# Transmissor_Ignitor.net
KiCad netlist of a schematic drawn in Altium Designer
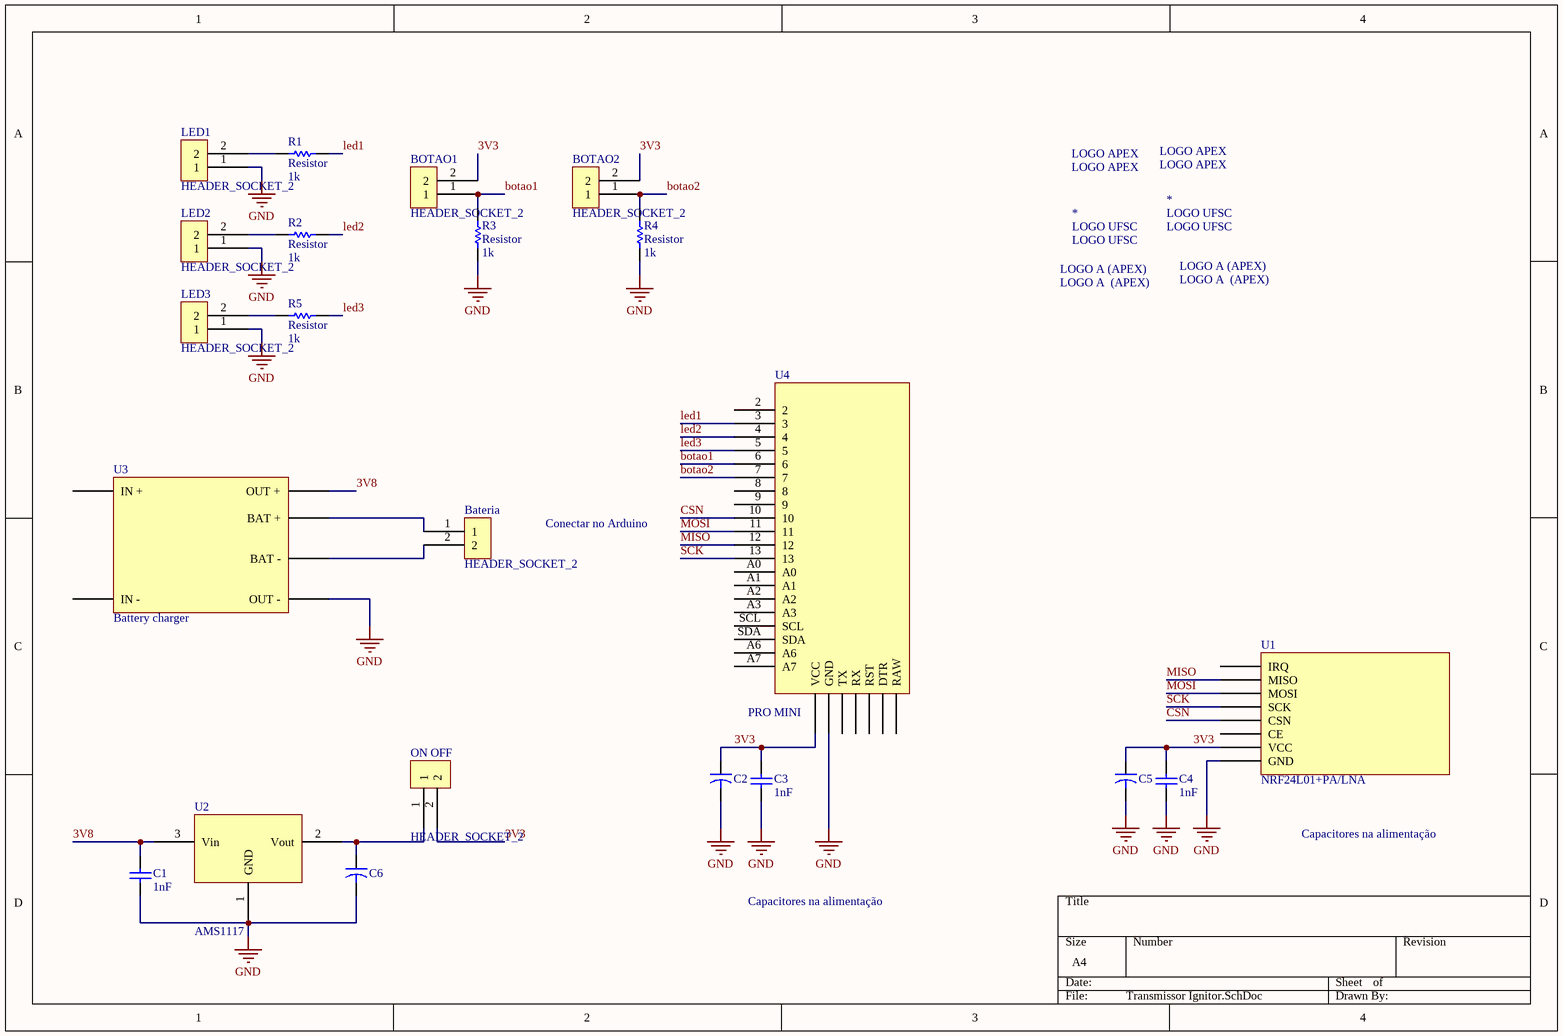
[diagram p0: Transmissor Ignitor.SchDoc]

(export (version "E")
  (design (tool "Eeschema 10.0.6"))
  (components
    (comp (ref "*1")
      (value "LOGO APEX")
      (footprint "Logo Apex")
      (libsource (lib "REV_1_20") (part "LOGO APEX"))
    )
    (comp (ref "*2")
      (value "LOGO APEX")
      (footprint "Logo Apex")
      (libsource (lib "REV_1_20") (part "LOGO APEX"))
    )
    (comp (ref "*5")
      (value "LOGO A  (APEX)")
      (footprint "LOGO A (apex)")
      (libsource (lib "REV_1_20") (part "LOGO A  (APEX)"))
    )
    (comp (ref "*6")
      (value "LOGO A  (APEX)")
      (footprint "LOGO A (apex)")
      (libsource (lib "REV_1_20") (part "LOGO A  (APEX)"))
    )
    (comp (ref "Bateria")
      (value "HEADER_SOCKET_2")
      (footprint "Pin Header 1x2 TH Pitch 2.54mm")
      (description "Socket to header connector with 2 pins")
      (libsource (lib "") (part "HEADER_SOCKET_2_2"))
    )
    (comp (ref "BOTAO1")
      (value "HEADER_SOCKET_2")
      (footprint "Pin Header 1x2 TH Pitch 2.54mm")
      (description "Socket to header connector with 2 pins")
      (libsource (lib "REV_1_20") (part "HEADER_SOCKET_2"))
    )
    (comp (ref "BOTAO2")
      (value "HEADER_SOCKET_2")
      (footprint "Pin Header 1x2 TH Pitch 2.54mm")
      (description "Socket to header connector with 2 pins")
      (libsource (lib "REV_1_20") (part "HEADER_SOCKET_2"))
    )
    (comp (ref "C1")
      (value "1nF")
      (footprint "CAP0805R")
      (description "Capacitor")
      (fields (field (name "Comment") "Cap_ceramic") (field (name "PUBLISHER") "Altium Limited"))
      (libsource (lib "REV_1_20") (part "Cap_ceramic"))
    )
    (comp (ref "C2")
      (value "CAP_ELEC")
      (footprint "CAPPR250-63X11")
      (description "Capacitor")
      (fields (field (name "PUBLISHER") "Altium Limited"))
      (libsource (lib "REV_1_20") (part "CAP_ELEC"))
    )
    (comp (ref "C3")
      (value "1nF")
      (footprint "CAP0805R")
      (description "Capacitor")
      (fields (field (name "Comment") "Cap_ceramic") (field (name "PUBLISHER") "Altium Limited"))
      (libsource (lib "REV_1_20") (part "Cap_ceramic"))
    )
    (comp (ref "C4")
      (value "1nF")
      (footprint "CAP0805R")
      (description "Capacitor")
      (fields (field (name "Comment") "Cap_ceramic") (field (name "PUBLISHER") "Altium Limited"))
      (libsource (lib "REV_1_20") (part "Cap_ceramic"))
    )
    (comp (ref "C5")
      (value "CAP_ELEC")
      (footprint "CAPPR250-63X11")
      (description "Capacitor")
      (fields (field (name "PUBLISHER") "Altium Limited"))
      (libsource (lib "REV_1_20") (part "CAP_ELEC"))
    )
    (comp (ref "C6")
      (value "CAP_ELEC")
      (footprint "CAPPR250-63X11")
      (description "Capacitor")
      (fields (field (name "PUBLISHER") "Altium Limited"))
      (libsource (lib "REV_1_20") (part "CAP_ELEC"))
    )
    (comp (ref "LED1")
      (value "HEADER_SOCKET_2")
      (footprint "Pin Header 1x2 TH Pitch 2.54mm")
      (description "Socket to header connector with 2 pins")
      (libsource (lib "REV_1_20") (part "HEADER_SOCKET_2"))
    )
    (comp (ref "LED2")
      (value "HEADER_SOCKET_2")
      (footprint "Pin Header 1x2 TH Pitch 2.54mm")
      (description "Socket to header connector with 2 pins")
      (libsource (lib "REV_1_20") (part "HEADER_SOCKET_2"))
    )
    (comp (ref "LED3")
      (value "HEADER_SOCKET_2")
      (footprint "Pin Header 1x2 TH Pitch 2.54mm")
      (description "Socket to header connector with 2 pins")
      (libsource (lib "REV_1_20") (part "HEADER_SOCKET_2"))
    )
    (comp (ref "ON OFF")
      (value "HEADER_SOCKET_2")
      (footprint "Pin Header 1x2 TH Pitch 2.54mm")
      (description "Socket to header connector with 2 pins")
      (libsource (lib "") (part "HEADER_SOCKET_2_1"))
    )
    (comp (ref "R1")
      (value "Resistor")
      (footprint "RES0805R")
      (fields (field (name "ALTIUM_VALUE") "1k") (field (name "PUBLISHER") "Altium Limited"))
      (libsource (lib "REV_1_20") (part "Resistor"))
    )
    (comp (ref "R2")
      (value "Resistor")
      (footprint "RES0805R")
      (fields (field (name "ALTIUM_VALUE") "1k") (field (name "PUBLISHER") "Altium Limited"))
      (libsource (lib "REV_1_20") (part "Resistor"))
    )
    (comp (ref "R3")
      (value "Resistor")
      (footprint "RES0805R")
      (fields (field (name "ALTIUM_VALUE") "1k") (field (name "PUBLISHER") "Altium Limited"))
      (libsource (lib "REV_1_20") (part "Resistor"))
    )
    (comp (ref "R4")
      (value "Resistor")
      (footprint "RES0805R")
      (fields (field (name "ALTIUM_VALUE") "1k") (field (name "PUBLISHER") "Altium Limited"))
      (libsource (lib "REV_1_20") (part "Resistor"))
    )
    (comp (ref "R5")
      (value "Resistor")
      (footprint "RES0805R")
      (fields (field (name "ALTIUM_VALUE") "1k") (field (name "PUBLISHER") "Altium Limited"))
      (libsource (lib "REV_1_20") (part "Resistor"))
    )
    (comp (ref "U1")
      (value "NRF24L01+PA/LNA")
      (footprint "NRF24L01")
      (libsource (lib "REV_1_20") (part "NRF24L01+PA/LNA"))
    )
    (comp (ref "U2") (value "AMS1117") (footprint "SOT-223-2") (libsource (lib "REV_1_20") (part "AMS1117")))
    (comp (ref "U3")
      (value "Battery charger")
      (footprint "Battery charger")
      (libsource (lib "REV_1_20") (part "Battery charger"))
    )
    (comp (ref "U4") (value "PRO MINI") (footprint "Pro mini") (libsource (lib "REV_1_20") (part "PRO MINI")))
  )
  (nets
    (net (code "1") (name "/3V3") (class "Default")
      (node (ref "BOTAO1") (pin "2") (pinfunction "2_2") (pintype "passive"))
      (node (ref "BOTAO2") (pin "2") (pinfunction "2_2") (pintype "passive"))
      (node (ref "C2") (pin "1") (pinfunction "1_1") (pintype "passive"))
      (node (ref "C3") (pin "2") (pinfunction "2_2") (pintype "passive"))
      (node (ref "C4") (pin "2") (pinfunction "2_2") (pintype "passive"))
      (node (ref "C5") (pin "1") (pinfunction "1_1") (pintype "passive"))
      (node (ref "ON OFF") (pin "2") (pinfunction "2_2") (pintype "passive"))
      (node (ref "U1") (pin "2") (pinfunction "VCC_2") (pintype "power_in"))
      (node (ref "U4") (pin "VCC") (pinfunction "VCC_VCC") (pintype "passive"))
    )
    (net (code "2") (name "/3V8") (class "Default")
      (node (ref "C1") (pin "2") (pinfunction "2_2") (pintype "passive"))
      (node (ref "U2") (pin "3") (pinfunction "Vin_3") (pintype "power_in"))
      (node (ref "U3") (pin "OUT_+") (pinfunction "OUT_+_OUT_+") (pintype "passive"))
    )
    (net (code "3") (name "/CSN") (class "Default")
      (node (ref "U1") (pin "4") (pinfunction "CSN_4") (pintype "passive"))
      (node (ref "U4") (pin "10") (pinfunction "10_10") (pintype "passive"))
    )
    (net (code "4") (name "/MISO") (class "Default")
      (node (ref "U1") (pin "7") (pinfunction "MISO_7") (pintype "passive"))
      (node (ref "U4") (pin "12") (pinfunction "12_12") (pintype "passive"))
    )
    (net (code "5") (name "/MOSI") (class "Default")
      (node (ref "U1") (pin "6") (pinfunction "MOSI_6") (pintype "passive"))
      (node (ref "U4") (pin "11") (pinfunction "11_11") (pintype "passive"))
    )
    (net (code "6") (name "/SCK") (class "Default")
      (node (ref "U1") (pin "5") (pinfunction "SCK_5") (pintype "passive"))
      (node (ref "U4") (pin "13") (pinfunction "13_13") (pintype "passive"))
    )
    (net (code "7") (name "/botao1") (class "Default")
      (node (ref "BOTAO1") (pin "1") (pinfunction "1_1") (pintype "passive"))
      (node (ref "R3") (pin "2") (pinfunction "2_2") (pintype "passive"))
      (node (ref "U4") (pin "6") (pinfunction "6_6") (pintype "passive"))
    )
    (net (code "8") (name "/botao2") (class "Default")
      (node (ref "BOTAO2") (pin "1") (pinfunction "1_1") (pintype "passive"))
      (node (ref "R4") (pin "2") (pinfunction "2_2") (pintype "passive"))
      (node (ref "U4") (pin "7") (pinfunction "7_7") (pintype "passive"))
    )
    (net (code "9") (name "/led1") (class "Default")
      (node (ref "R1") (pin "2") (pinfunction "2_2") (pintype "passive"))
      (node (ref "U4") (pin "3") (pinfunction "3_3") (pintype "passive"))
    )
    (net (code "10") (name "/led2") (class "Default")
      (node (ref "R2") (pin "2") (pinfunction "2_2") (pintype "passive"))
      (node (ref "U4") (pin "4") (pinfunction "4_4") (pintype "passive"))
    )
    (net (code "11") (name "/led3") (class "Default")
      (node (ref "R5") (pin "2") (pinfunction "2_2") (pintype "passive"))
      (node (ref "U4") (pin "5") (pinfunction "5_5") (pintype "passive"))
    )
    (net (code "12") (name "GND") (class "Default")
      (node (ref "C1") (pin "1") (pinfunction "1_1") (pintype "passive"))
      (node (ref "C2") (pin "2") (pinfunction "2_2") (pintype "passive"))
      (node (ref "C3") (pin "1") (pinfunction "1_1") (pintype "passive"))
      (node (ref "C4") (pin "1") (pinfunction "1_1") (pintype "passive"))
      (node (ref "C5") (pin "2") (pinfunction "2_2") (pintype "passive"))
      (node (ref "C6") (pin "2") (pinfunction "2_2") (pintype "passive"))
      (node (ref "LED1") (pin "1") (pinfunction "1_1") (pintype "passive"))
      (node (ref "LED2") (pin "1") (pinfunction "1_1") (pintype "passive"))
      (node (ref "LED3") (pin "1") (pinfunction "1_1") (pintype "passive"))
      (node (ref "R3") (pin "1") (pinfunction "1_1") (pintype "passive"))
      (node (ref "R4") (pin "1") (pinfunction "1_1") (pintype "passive"))
      (node (ref "U1") (pin "1") (pinfunction "GND_1") (pintype "power_in"))
      (node (ref "U2") (pin "1") (pinfunction "GND_1") (pintype "power_in"))
      (node (ref "U3") (pin "OUT_-") (pinfunction "OUT_-_OUT_-") (pintype "passive"))
      (node (ref "U4") (pin "GND") (pinfunction "GND_GND") (pintype "passive"))
    )
    (net (code "13") (name "Net-(Bateria-Pad1)") (class "Default")
      (node (ref "Bateria") (pin "1") (pinfunction "1_1") (pintype "passive"))
      (node (ref "U3") (pin "BAT_+") (pinfunction "BAT_+_BAT_+") (pintype "passive"))
    )
    (net (code "14") (name "Net-(Bateria-Pad2)") (class "Default")
      (node (ref "Bateria") (pin "2") (pinfunction "2_2") (pintype "passive"))
      (node (ref "U3") (pin "BAT_-") (pinfunction "BAT_-_BAT_-") (pintype "passive"))
    )
    (net (code "15") (name "Net-(LED1-Pad2)") (class "Default")
      (node (ref "LED1") (pin "2") (pinfunction "2_2") (pintype "passive"))
      (node (ref "R1") (pin "1") (pinfunction "1_1") (pintype "passive"))
    )
    (net (code "16") (name "Net-(LED2-Pad2)") (class "Default")
      (node (ref "LED2") (pin "2") (pinfunction "2_2") (pintype "passive"))
      (node (ref "R2") (pin "1") (pinfunction "1_1") (pintype "passive"))
    )
    (net (code "17") (name "Net-(LED3-Pad2)") (class "Default")
      (node (ref "LED3") (pin "2") (pinfunction "2_2") (pintype "passive"))
      (node (ref "R5") (pin "1") (pinfunction "1_1") (pintype "passive"))
    )
    (net (code "18") (name "Net-(U2-Vout)") (class "Default")
      (node (ref "C6") (pin "1") (pinfunction "1_1") (pintype "passive"))
      (node (ref "ON OFF") (pin "1") (pinfunction "1_1") (pintype "passive"))
      (node (ref "U2") (pin "2") (pinfunction "Vout_2") (pintype "power_in"))
    )
    (net (code "19") (name "unconnected-(U1-CE-Pad3)") (class "Default")
      (node (ref "U1") (pin "3") (pinfunction "CE_3") (pintype "passive"))
    )
    (net (code "20") (name "unconnected-(U1-IRQ-Pad8)") (class "Default")
      (node (ref "U1") (pin "8") (pinfunction "IRQ_8") (pintype "passive"))
    )
    (net (code "21") (name "unconnected-(U3-PadIN_+)") (class "Default")
      (node (ref "U3") (pin "IN_+") (pinfunction "IN_+_IN_+") (pintype "passive"))
    )
    (net (code "22") (name "unconnected-(U3-PadIN_-)") (class "Default")
      (node (ref "U3") (pin "IN_-") (pinfunction "IN_-_IN_-") (pintype "passive"))
    )
    (net (code "23") (name "unconnected-(U4-Pad2)") (class "Default")
      (node (ref "U4") (pin "2") (pinfunction "2_2") (pintype "passive"))
    )
    (net (code "24") (name "unconnected-(U4-Pad8)") (class "Default")
      (node (ref "U4") (pin "8") (pinfunction "8_8") (pintype "passive"))
    )
    (net (code "25") (name "unconnected-(U4-Pad9)") (class "Default")
      (node (ref "U4") (pin "9") (pinfunction "9_9") (pintype "passive"))
    )
    (net (code "26") (name "unconnected-(U4-PadA0)") (class "Default")
      (node (ref "U4") (pin "A0") (pinfunction "A0_A0") (pintype "passive"))
    )
    (net (code "27") (name "unconnected-(U4-PadA1)") (class "Default")
      (node (ref "U4") (pin "A1") (pinfunction "A1_A1") (pintype "passive"))
    )
    (net (code "28") (name "unconnected-(U4-PadA2)") (class "Default")
      (node (ref "U4") (pin "A2") (pinfunction "A2_A2") (pintype "passive"))
    )
    (net (code "29") (name "unconnected-(U4-PadA3)") (class "Default")
      (node (ref "U4") (pin "A3") (pinfunction "A3_A3") (pintype "passive"))
    )
    (net (code "30") (name "unconnected-(U4-PadA6)") (class "Default")
      (node (ref "U4") (pin "A6") (pinfunction "A6_A6") (pintype "passive"))
    )
    (net (code "31") (name "unconnected-(U4-PadA7)") (class "Default")
      (node (ref "U4") (pin "A7") (pinfunction "A7_A7") (pintype "passive"))
    )
    (net (code "32") (name "unconnected-(U4-PadDTR)") (class "Default")
      (node (ref "U4") (pin "DTR") (pinfunction "DTR_DTR") (pintype "passive"))
    )
    (net (code "33") (name "unconnected-(U4-PadRAW)") (class "Default")
      (node (ref "U4") (pin "RAW") (pinfunction "RAW_RAW") (pintype "passive"))
    )
    (net (code "34") (name "unconnected-(U4-PadRST)") (class "Default")
      (node (ref "U4") (pin "RST") (pinfunction "RST_RST") (pintype "passive"))
    )
    (net (code "35") (name "unconnected-(U4-PadRX)") (class "Default")
      (node (ref "U4") (pin "RX") (pinfunction "RX_RX") (pintype "passive"))
    )
    (net (code "36") (name "unconnected-(U4-PadSCL)") (class "Default")
      (node (ref "U4") (pin "SCL") (pinfunction "SCL_SCL") (pintype "passive"))
    )
    (net (code "37") (name "unconnected-(U4-PadSDA)") (class "Default")
      (node (ref "U4") (pin "SDA") (pinfunction "SDA_SDA") (pintype "passive"))
    )
    (net (code "38") (name "unconnected-(U4-PadTX)") (class "Default")
      (node (ref "U4") (pin "TX") (pinfunction "TX_TX") (pintype "passive"))
    )
  )
)
